# Controller-Board_Rack-PDU_2_0.net
KiCad netlist of a schematic drawn in EAGLE
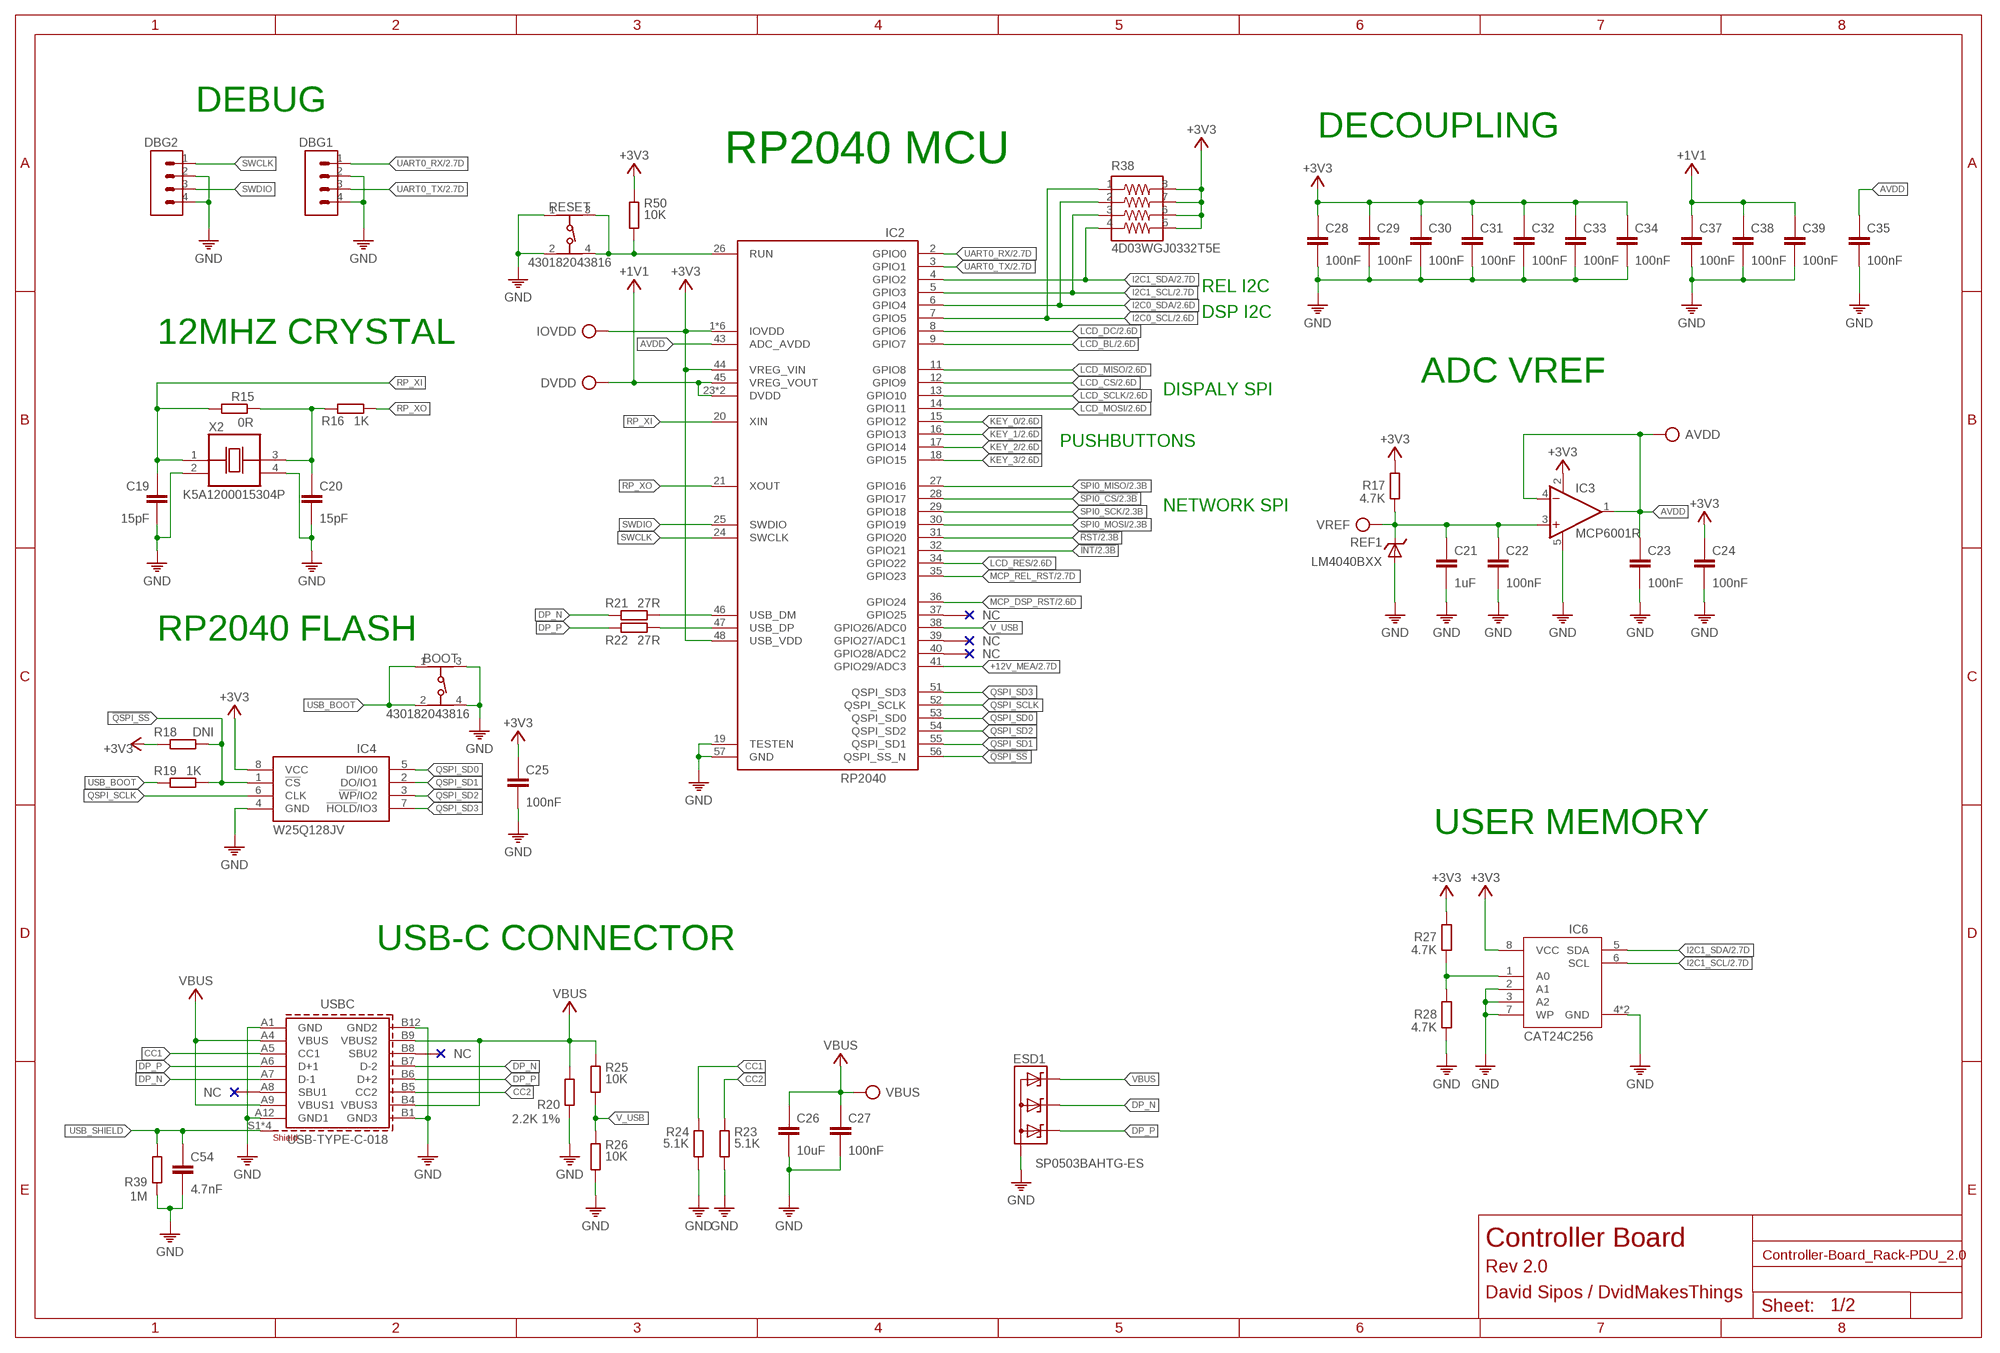
[diagram p0: schematic, sheet 1]
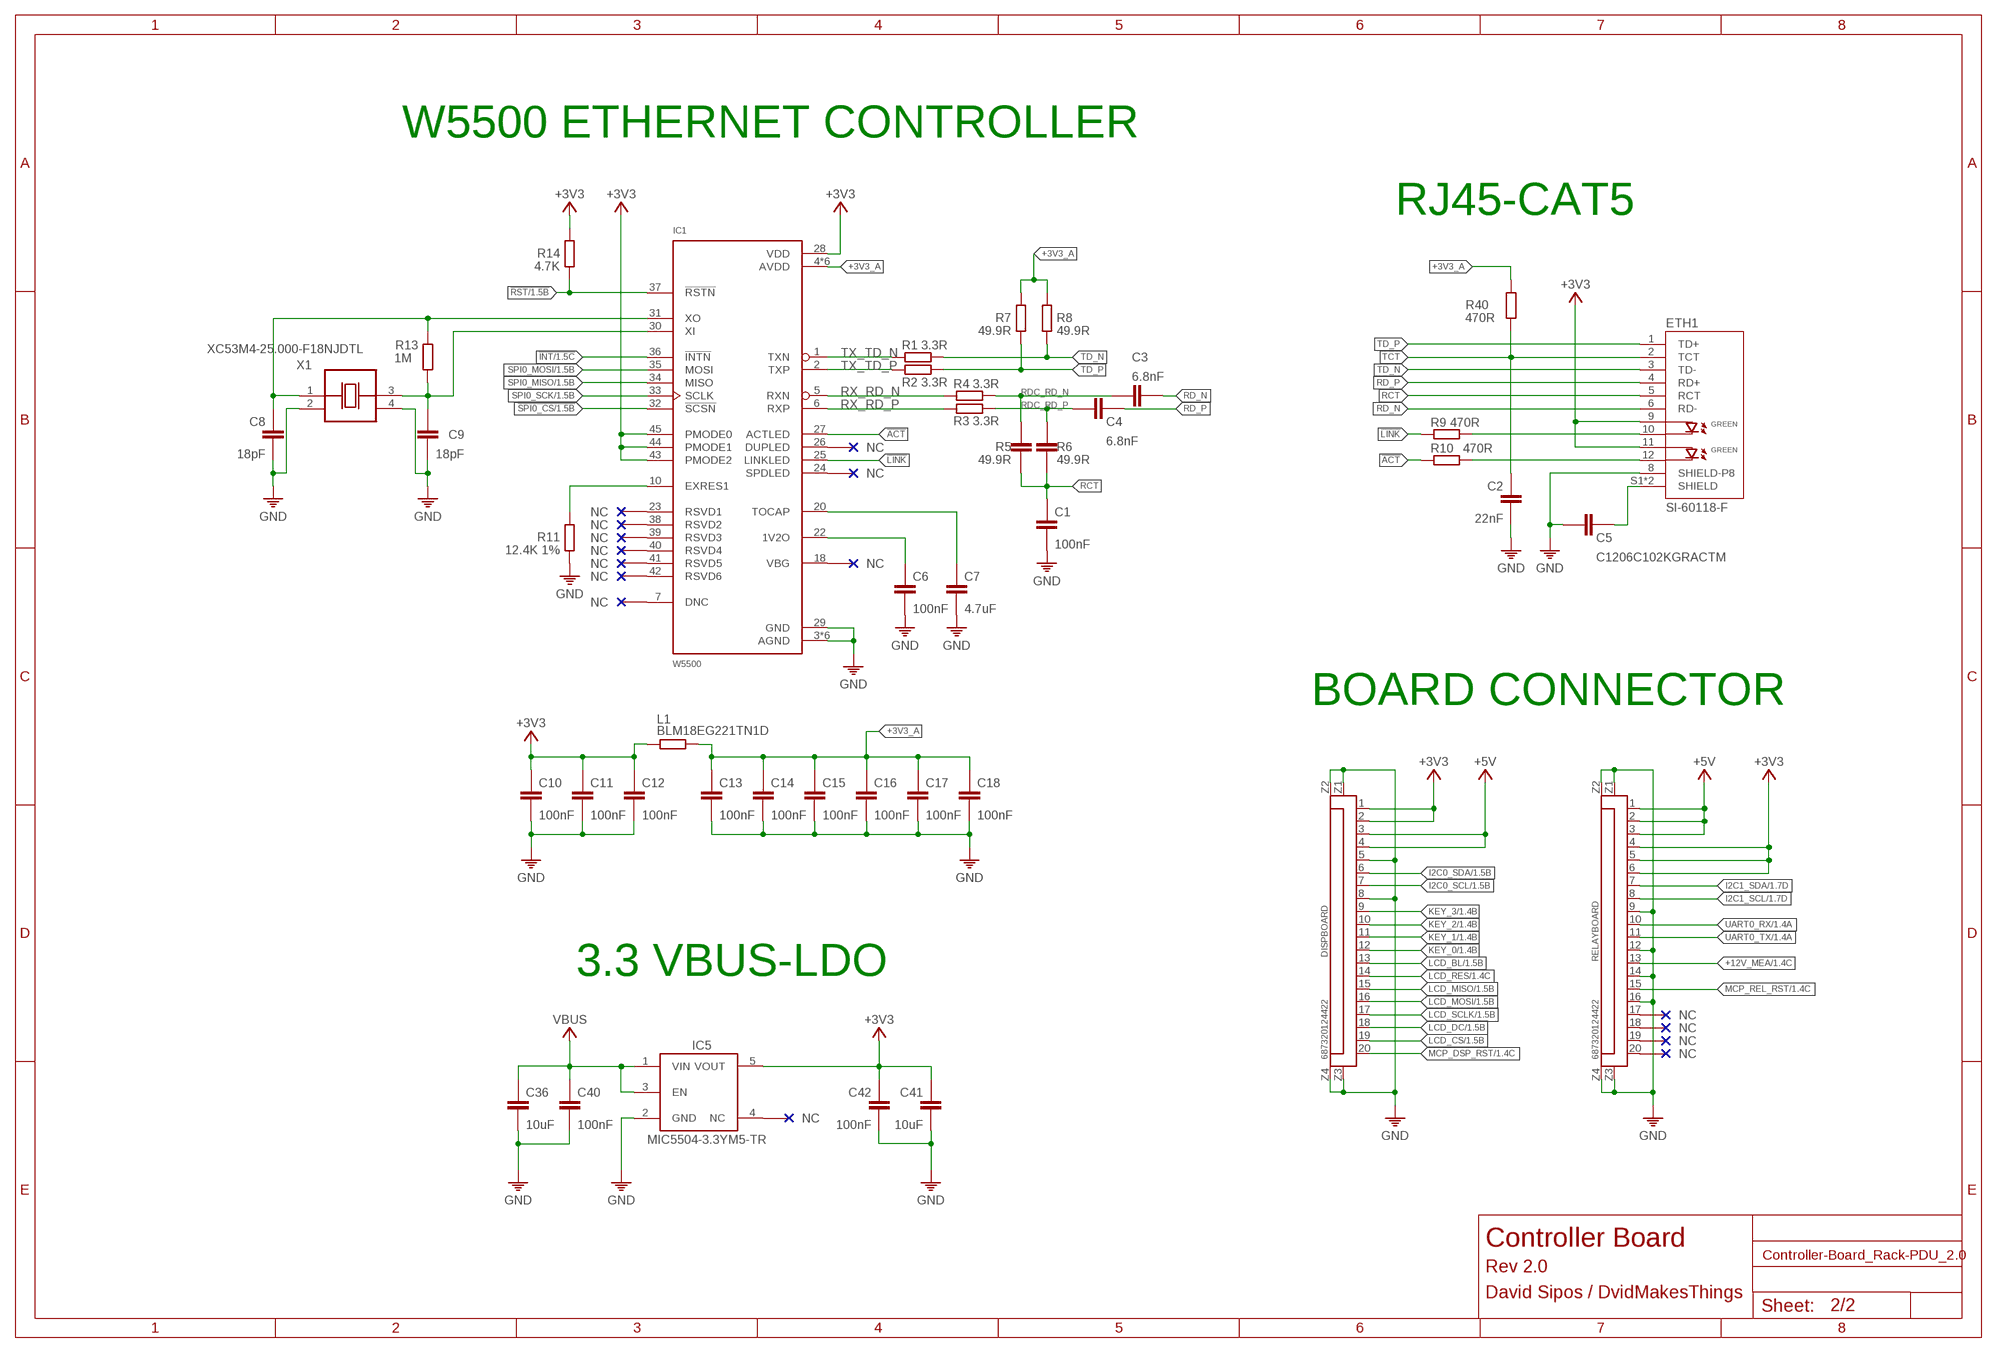
[diagram p1: schematic, sheet 2]

(export (version "E")
  (design (tool "Eeschema 10.0.6"))
  (components
    (comp (ref "AVDD")
      (value "TP")
      (footprint "eagle-import:TP")
      (libsource (lib "eagle-import") (part "TP"))
    )
    (comp (ref "BOOT")
      (value "430182043816")
      (footprint "eagle-import:430182043816")
      (libsource (lib "eagle-import") (part "430182043816"))
    )
    (comp (ref "C19")
      (value "15pF")
      (footprint "eagle-import:C0402")
      (libsource (lib "eagle-import") (part "C-0402"))
    )
    (comp (ref "C20")
      (value "15pF")
      (footprint "eagle-import:C0402")
      (libsource (lib "eagle-import") (part "C-0402"))
    )
    (comp (ref "C21")
      (value "1uF")
      (footprint "eagle-import:C0402")
      (libsource (lib "eagle-import") (part "C-0402"))
    )
    (comp (ref "C22")
      (value "100nF")
      (footprint "eagle-import:C0402")
      (libsource (lib "eagle-import") (part "C-0402"))
    )
    (comp (ref "C23")
      (value "100nF")
      (footprint "eagle-import:C0402")
      (libsource (lib "eagle-import") (part "C-0402"))
    )
    (comp (ref "C24")
      (value "100nF")
      (footprint "eagle-import:C0402")
      (libsource (lib "eagle-import") (part "C-0402"))
    )
    (comp (ref "C25")
      (value "100nF")
      (footprint "eagle-import:C0402")
      (libsource (lib "eagle-import") (part "C-0402"))
    )
    (comp (ref "C26")
      (value "10uF")
      (footprint "eagle-import:0805")
      (libsource (lib "eagle-import") (part "C0805"))
    )
    (comp (ref "C27")
      (value "100nF")
      (footprint "eagle-import:0402")
      (libsource (lib "eagle-import") (part "C0402"))
    )
    (comp (ref "C28")
      (value "100nF")
      (footprint "eagle-import:C0402")
      (libsource (lib "eagle-import") (part "C-0402"))
    )
    (comp (ref "C29")
      (value "100nF")
      (footprint "eagle-import:C0402")
      (libsource (lib "eagle-import") (part "C-0402"))
    )
    (comp (ref "C30")
      (value "100nF")
      (footprint "eagle-import:C0402")
      (libsource (lib "eagle-import") (part "C-0402"))
    )
    (comp (ref "C31")
      (value "100nF")
      (footprint "eagle-import:C0402")
      (libsource (lib "eagle-import") (part "C-0402"))
    )
    (comp (ref "C32")
      (value "100nF")
      (footprint "eagle-import:C0402")
      (libsource (lib "eagle-import") (part "C-0402"))
    )
    (comp (ref "C33")
      (value "100nF")
      (footprint "eagle-import:C0402")
      (libsource (lib "eagle-import") (part "C-0402"))
    )
    (comp (ref "C34")
      (value "100nF")
      (footprint "eagle-import:C0402")
      (libsource (lib "eagle-import") (part "C-0402"))
    )
    (comp (ref "C35")
      (value "100nF")
      (footprint "eagle-import:C0402")
      (libsource (lib "eagle-import") (part "C-0402"))
    )
    (comp (ref "C37")
      (value "100nF")
      (footprint "eagle-import:C0402")
      (libsource (lib "eagle-import") (part "C-0402"))
    )
    (comp (ref "C38")
      (value "100nF")
      (footprint "eagle-import:C0402")
      (libsource (lib "eagle-import") (part "C-0402"))
    )
    (comp (ref "C39")
      (value "100nF")
      (footprint "eagle-import:C0402")
      (libsource (lib "eagle-import") (part "C-0402"))
    )
    (comp (ref "C54")
      (value "4.7nF")
      (footprint "eagle-import:0402")
      (libsource (lib "eagle-import") (part "C0402"))
    )
    (comp (ref "DBG1")
      (value "CON-1X4")
      (footprint "eagle-import:1X4")
      (libsource (lib "eagle-import") (part "CON-1X4"))
    )
    (comp (ref "DBG2")
      (value "CON-1X4")
      (footprint "eagle-import:1X4")
      (libsource (lib "eagle-import") (part "CON-1X4"))
    )
    (comp (ref "DVDD")
      (value "TP")
      (footprint "eagle-import:TP")
      (libsource (lib "eagle-import") (part "TP"))
    )
    (comp (ref "ESD1")
      (value "SP0503BAHTG-ES")
      (footprint "eagle-import:SOT143")
      (libsource (lib "eagle-import") (part "SP0503BAHT"))
    )
    (comp (ref "IC2")
      (value "RP2040")
      (footprint "eagle-import:QFN40P700X700X100-57T510")
      (libsource (lib "eagle-import") (part "RP2040"))
    )
    (comp (ref "IC3")
      (value "MCP6001R")
      (footprint "eagle-import:SOT23-5")
      (libsource (lib "eagle-import") (part "MCP6001RT"))
    )
    (comp (ref "IC4")
      (value "W25Q128JVPIQ")
      (footprint "eagle-import:SON127P600X500X75-8N")
      (libsource (lib "eagle-import") (part "W25Q128JVP"))
    )
    (comp (ref "IC6")
      (value "CAT24C256HU4IGT3")
      (footprint "eagle-import:SON50P300X200X50-9T130X140N")
      (libsource (lib "eagle-import") (part "CAT24C256-HU4"))
    )
    (comp (ref "IOVDD")
      (value "TP")
      (footprint "eagle-import:TP")
      (libsource (lib "eagle-import") (part "TP"))
    )
    (comp (ref "R15")
      (value "0R")
      (footprint "eagle-import:0402")
      (libsource (lib "eagle-import") (part "R0402"))
    )
    (comp (ref "R16")
      (value "1K")
      (footprint "eagle-import:0402")
      (libsource (lib "eagle-import") (part "R0402"))
    )
    (comp (ref "R17")
      (value "4.7K")
      (footprint "eagle-import:0402")
      (libsource (lib "eagle-import") (part "R0402"))
    )
    (comp (ref "R18")
      (value "DNI")
      (footprint "eagle-import:0402")
      (libsource (lib "eagle-import") (part "R0402"))
    )
    (comp (ref "R19")
      (value "1K")
      (footprint "eagle-import:0402")
      (libsource (lib "eagle-import") (part "R0402"))
    )
    (comp (ref "R20")
      (value "2.2K 1%")
      (footprint "eagle-import:0402")
      (libsource (lib "eagle-import") (part "ds_passive_46685041_R0402"))
    )
    (comp (ref "R21")
      (value "27R")
      (footprint "eagle-import:0402")
      (libsource (lib "eagle-import") (part "R0402"))
    )
    (comp (ref "R22")
      (value "27R")
      (footprint "eagle-import:0402")
      (libsource (lib "eagle-import") (part "R0402"))
    )
    (comp (ref "R23")
      (value "5.1K")
      (footprint "eagle-import:0402")
      (libsource (lib "eagle-import") (part "ds_passive_46685041_R0402"))
    )
    (comp (ref "R24")
      (value "5.1K")
      (footprint "eagle-import:0402")
      (libsource (lib "eagle-import") (part "ds_passive_46685041_R0402"))
    )
    (comp (ref "R25")
      (value "10K")
      (footprint "eagle-import:0402")
      (libsource (lib "eagle-import") (part "ds_passive_46685041_R0402"))
    )
    (comp (ref "R26")
      (value "10K")
      (footprint "eagle-import:0402")
      (libsource (lib "eagle-import") (part "ds_passive_46685041_R0402"))
    )
    (comp (ref "R27")
      (value "4.7K")
      (footprint "eagle-import:0402")
      (libsource (lib "eagle-import") (part "R0402"))
    )
    (comp (ref "R28")
      (value "4.7K")
      (footprint "eagle-import:0402")
      (libsource (lib "eagle-import") (part "R0402"))
    )
    (comp (ref "R38")
      (value "4D03WGJ0332T5E")
      (footprint "eagle-import:742C083103JP")
      (fields
        (field (name "MANUFACTURER") "CTS Resistor Products")
        (field (name "MPN") "742C083103JP")
        (field (name "CREATED_BY") "PCBLayout.com")
      )
      (libsource (lib "eagle-import") (part "742C083103JP"))
    )
    (comp (ref "R39")
      (value "1M")
      (footprint "eagle-import:0402")
      (libsource (lib "eagle-import") (part "ds_passive_46685041_R0402"))
    )
    (comp (ref "R50")
      (value "10K")
      (footprint "eagle-import:0402")
      (libsource (lib "eagle-import") (part "ds_passive_46685041_R0402"))
    )
    (comp (ref "REF1")
      (value "LM4040BXX")
      (footprint "eagle-import:SOT23")
      (libsource (lib "eagle-import") (part "LM4040BXX"))
    )
    (comp (ref "RESET")
      (value "430182043816")
      (footprint "eagle-import:430182043816")
      (libsource (lib "eagle-import") (part "430182043816"))
    )
    (comp (ref "USBC")
      (value "USB-TYPE-C-018")
      (footprint "eagle-import:629722000214")
      (libsource (lib "eagle-import") (part "629722000214"))
    )
    (comp (ref "VBUS")
      (value "TP")
      (footprint "eagle-import:TP")
      (libsource (lib "eagle-import") (part "TP"))
    )
    (comp (ref "VREF")
      (value "TP")
      (footprint "eagle-import:TP")
      (libsource (lib "eagle-import") (part "TP"))
    )
    (comp (ref "X2")
      (value "K5A1200015304P")
      (footprint "eagle-import:OSCCC500X320X130")
      (libsource (lib "eagle-import") (part "CRYSTAL"))
    )
    (comp (ref "C1")
      (value "100nF")
      (footprint "eagle-import:C0402")
      (libsource (lib "eagle-import") (part "C-0402"))
    )
    (comp (ref "C2")
      (value "22nF")
      (footprint "eagle-import:C0402")
      (libsource (lib "eagle-import") (part "C-0402"))
    )
    (comp (ref "C3")
      (value "6.8nF")
      (footprint "eagle-import:C0402")
      (libsource (lib "eagle-import") (part "C-0402"))
    )
    (comp (ref "C4")
      (value "6.8nF")
      (footprint "eagle-import:C0402")
      (libsource (lib "eagle-import") (part "C-0402"))
    )
    (comp (ref "C5")
      (value "C1206C102KGRACTM")
      (footprint "eagle-import:C1206")
      (libsource (lib "eagle-import") (part "C-1206"))
    )
    (comp (ref "C6")
      (value "100nF")
      (footprint "eagle-import:C0402")
      (libsource (lib "eagle-import") (part "C-0402"))
    )
    (comp (ref "C7")
      (value "4.7uF")
      (footprint "eagle-import:C0402")
      (libsource (lib "eagle-import") (part "C-0402"))
    )
    (comp (ref "C8")
      (value "18pF")
      (footprint "eagle-import:C0402")
      (libsource (lib "eagle-import") (part "C-0402"))
    )
    (comp (ref "C9")
      (value "18pF")
      (footprint "eagle-import:C0402")
      (libsource (lib "eagle-import") (part "C-0402"))
    )
    (comp (ref "C10")
      (value "100nF")
      (footprint "eagle-import:C0402")
      (libsource (lib "eagle-import") (part "C-0402"))
    )
    (comp (ref "C11")
      (value "100nF")
      (footprint "eagle-import:C0402")
      (libsource (lib "eagle-import") (part "C-0402"))
    )
    (comp (ref "C12")
      (value "100nF")
      (footprint "eagle-import:C0402")
      (libsource (lib "eagle-import") (part "C-0402"))
    )
    (comp (ref "C13")
      (value "100nF")
      (footprint "eagle-import:C0402")
      (libsource (lib "eagle-import") (part "C-0402"))
    )
    (comp (ref "C14")
      (value "100nF")
      (footprint "eagle-import:C0402")
      (libsource (lib "eagle-import") (part "C-0402"))
    )
    (comp (ref "C15")
      (value "100nF")
      (footprint "eagle-import:C0402")
      (libsource (lib "eagle-import") (part "C-0402"))
    )
    (comp (ref "C16")
      (value "100nF")
      (footprint "eagle-import:C0402")
      (libsource (lib "eagle-import") (part "C-0402"))
    )
    (comp (ref "C17")
      (value "100nF")
      (footprint "eagle-import:C0402")
      (libsource (lib "eagle-import") (part "C-0402"))
    )
    (comp (ref "C18")
      (value "100nF")
      (footprint "eagle-import:C0402")
      (libsource (lib "eagle-import") (part "C-0402"))
    )
    (comp (ref "C36")
      (value "10uF")
      (footprint "eagle-import:0805")
      (libsource (lib "eagle-import") (part "C0805"))
    )
    (comp (ref "C40")
      (value "100nF")
      (footprint "eagle-import:0402")
      (libsource (lib "eagle-import") (part "C0402"))
    )
    (comp (ref "C41")
      (value "10uF")
      (footprint "eagle-import:0805")
      (libsource (lib "eagle-import") (part "C0805"))
    )
    (comp (ref "C42")
      (value "100nF")
      (footprint "eagle-import:0402")
      (libsource (lib "eagle-import") (part "C0402"))
    )
    (comp (ref "DISPBOARD")
      (value "687320124422")
      (footprint "eagle-import:687320124422")
      (libsource (lib "eagle-import") (part "6873XX124422_687320124422"))
    )
    (comp (ref "ETH1")
      (value "SI-60118-F")
      (footprint "eagle-import:RJ45-CAT5")
      (fields (field (name "MANUFACTURER") "Bel Fuse"))
      (libsource (lib "eagle-import") (part "RJ45-CAT5"))
    )
    (comp (ref "IC1")
      (value "W5500")
      (footprint "eagle-import:LQFP48")
      (libsource (lib "eagle-import") (part "W5500"))
    )
    (comp (ref "IC5")
      (value "MIC5504-3.3YM5-TR")
      (footprint "eagle-import:SOT23-5")
      (libsource (lib "eagle-import") (part "MIC5504-3.3YM5-TR"))
    )
    (comp (ref "L1")
      (value "BLM18EG221TN1D")
      (footprint "eagle-import:0603")
      (libsource (lib "eagle-import") (part "R0603"))
    )
    (comp (ref "R1")
      (value "3.3R")
      (footprint "eagle-import:0402")
      (libsource (lib "eagle-import") (part "R0402"))
    )
    (comp (ref "R2")
      (value "3.3R")
      (footprint "eagle-import:0402")
      (libsource (lib "eagle-import") (part "R0402"))
    )
    (comp (ref "R3")
      (value "3.3R")
      (footprint "eagle-import:0402")
      (libsource (lib "eagle-import") (part "R0402"))
    )
    (comp (ref "R4")
      (value "3.3R")
      (footprint "eagle-import:0402")
      (libsource (lib "eagle-import") (part "R0402"))
    )
    (comp (ref "R5")
      (value "49.9R")
      (footprint "eagle-import:C0402")
      (libsource (lib "eagle-import") (part "C-0402"))
    )
    (comp (ref "R6")
      (value "49.9R")
      (footprint "eagle-import:C0402")
      (libsource (lib "eagle-import") (part "C-0402"))
    )
    (comp (ref "R7")
      (value "49.9R")
      (footprint "eagle-import:0402")
      (libsource (lib "eagle-import") (part "R0402"))
    )
    (comp (ref "R8")
      (value "49.9R")
      (footprint "eagle-import:0402")
      (libsource (lib "eagle-import") (part "R0402"))
    )
    (comp (ref "R9")
      (value "470R")
      (footprint "eagle-import:0402")
      (libsource (lib "eagle-import") (part "R0402"))
    )
    (comp (ref "R10")
      (value "470R")
      (footprint "eagle-import:0402")
      (libsource (lib "eagle-import") (part "R0402"))
    )
    (comp (ref "R11")
      (value "12.4K 1%")
      (footprint "eagle-import:0402")
      (libsource (lib "eagle-import") (part "R0402"))
    )
    (comp (ref "R13")
      (value "1M")
      (footprint "eagle-import:0402")
      (libsource (lib "eagle-import") (part "R0402"))
    )
    (comp (ref "R14")
      (value "4.7K")
      (footprint "eagle-import:0402")
      (libsource (lib "eagle-import") (part "R0402"))
    )
    (comp (ref "R40")
      (value "470R")
      (footprint "eagle-import:0402")
      (libsource (lib "eagle-import") (part "R0402"))
    )
    (comp (ref "RELAYBOARD")
      (value "687320124422")
      (footprint "eagle-import:687320124422")
      (libsource (lib "eagle-import") (part "6873XX124422_687320124422"))
    )
    (comp (ref "X1")
      (value "XC53M4-25.000-F18NJDTL")
      (footprint "eagle-import:OSCCC500X320X130")
      (libsource (lib "eagle-import") (part "CRYSTAL"))
    )
  )
  (nets
    (net (code "1") (name "+1V1") (class "Default")
      (node (ref "C37") (pin "1") (pinfunction "1_1") (pintype "passive"))
      (node (ref "C38") (pin "1") (pinfunction "1_1") (pintype "passive"))
      (node (ref "C39") (pin "1") (pinfunction "1_1") (pintype "passive"))
      (node (ref "DVDD") (pin "TP") (pinfunction "P$1_TP") (pintype "bidirectional"))
      (node (ref "IC2") (pin "23") (pinfunction "DVDD_23") (pintype "bidirectional"))
      (node (ref "IC2") (pin "45") (pinfunction "VREG_VOUT_45") (pintype "bidirectional"))
      (node (ref "IC2") (pin "50") (pinfunction "DVDD_50") (pintype "bidirectional"))
    )
    (net (code "2") (name "+3V3") (class "Default")
      (node (ref "C10") (pin "1") (pinfunction "1_1") (pintype "passive"))
      (node (ref "C11") (pin "1") (pinfunction "1_1") (pintype "passive"))
      (node (ref "C12") (pin "1") (pinfunction "1_1") (pintype "passive"))
      (node (ref "C24") (pin "1") (pinfunction "1_1") (pintype "passive"))
      (node (ref "C25") (pin "1") (pinfunction "1_1") (pintype "passive"))
      (node (ref "C28") (pin "1") (pinfunction "1_1") (pintype "passive"))
      (node (ref "C29") (pin "1") (pinfunction "1_1") (pintype "passive"))
      (node (ref "C30") (pin "1") (pinfunction "1_1") (pintype "passive"))
      (node (ref "C31") (pin "1") (pinfunction "1_1") (pintype "passive"))
      (node (ref "C32") (pin "1") (pinfunction "1_1") (pintype "passive"))
      (node (ref "C33") (pin "1") (pinfunction "1_1") (pintype "passive"))
      (node (ref "C34") (pin "1") (pinfunction "1_1") (pintype "passive"))
      (node (ref "C41") (pin "1") (pinfunction "1_1") (pintype "passive"))
      (node (ref "C42") (pin "1") (pinfunction "1_1") (pintype "passive"))
      (node (ref "DISPBOARD") (pin "1") (pinfunction "1_1") (pintype "passive"))
      (node (ref "DISPBOARD") (pin "2") (pinfunction "2_2") (pintype "passive"))
      (node (ref "ETH1") (pin "11") (pinfunction "GA2_11") (pintype "passive"))
      (node (ref "ETH1") (pin "9") (pinfunction "GA1_9") (pintype "passive"))
      (node (ref "IC1") (pin "28") (pinfunction "VDD_28") (pintype "power_in"))
      (node (ref "IC1") (pin "43") (pinfunction "PMODE2_43") (pintype "input"))
      (node (ref "IC1") (pin "44") (pinfunction "PMODE1_44") (pintype "input"))
      (node (ref "IC1") (pin "45") (pinfunction "PMODE0_45") (pintype "input"))
      (node (ref "IC2") (pin "1") (pinfunction "IOVDD_1") (pintype "bidirectional"))
      (node (ref "IC2") (pin "10") (pinfunction "IOVDD_10") (pintype "bidirectional"))
      (node (ref "IC2") (pin "22") (pinfunction "IOVDD_22") (pintype "bidirectional"))
      (node (ref "IC2") (pin "33") (pinfunction "IOVDD_33") (pintype "bidirectional"))
      (node (ref "IC2") (pin "42") (pinfunction "IOVDD_42") (pintype "bidirectional"))
      (node (ref "IC2") (pin "44") (pinfunction "VREG_VIN_44") (pintype "bidirectional"))
      (node (ref "IC2") (pin "48") (pinfunction "USB_VDD_48") (pintype "bidirectional"))
      (node (ref "IC2") (pin "49") (pinfunction "IOVDD_49") (pintype "bidirectional"))
      (node (ref "IC3") (pin "2") (pinfunction "V+_2") (pintype "power_in"))
      (node (ref "IC4") (pin "8") (pinfunction "VCC_8") (pintype "power_in"))
      (node (ref "IC5") (pin "5") (pinfunction "VOUT_5") (pintype "bidirectional"))
      (node (ref "IC6") (pin "8") (pinfunction "VCC_8") (pintype "power_in"))
      (node (ref "IOVDD") (pin "TP") (pinfunction "P$1_TP") (pintype "bidirectional"))
      (node (ref "L1") (pin "1") (pinfunction "1_1") (pintype "passive"))
      (node (ref "R14") (pin "2") (pinfunction "2_2") (pintype "passive"))
      (node (ref "R17") (pin "2") (pinfunction "2_2") (pintype "passive"))
      (node (ref "R18") (pin "2") (pinfunction "2_2") (pintype "passive"))
      (node (ref "R27") (pin "2") (pinfunction "2_2") (pintype "passive"))
      (node (ref "R38") (pin "5") (pinfunction "5_5") (pintype "passive"))
      (node (ref "R38") (pin "6") (pinfunction "6_6") (pintype "passive"))
      (node (ref "R38") (pin "7") (pinfunction "7_7") (pintype "passive"))
      (node (ref "R38") (pin "8") (pinfunction "8_8") (pintype "passive"))
      (node (ref "R50") (pin "1") (pinfunction "1_1") (pintype "passive"))
      (node (ref "RELAYBOARD") (pin "4") (pinfunction "4_4") (pintype "passive"))
      (node (ref "RELAYBOARD") (pin "5") (pinfunction "5_5") (pintype "passive"))
      (node (ref "RELAYBOARD") (pin "6") (pinfunction "6_6") (pintype "passive"))
    )
    (net (code "3") (name "+3V3_A") (class "Default")
      (node (ref "C13") (pin "1") (pinfunction "1_1") (pintype "passive"))
      (node (ref "C14") (pin "1") (pinfunction "1_1") (pintype "passive"))
      (node (ref "C15") (pin "1") (pinfunction "1_1") (pintype "passive"))
      (node (ref "C16") (pin "1") (pinfunction "1_1") (pintype "passive"))
      (node (ref "C17") (pin "1") (pinfunction "1_1") (pintype "passive"))
      (node (ref "C18") (pin "1") (pinfunction "1_1") (pintype "passive"))
      (node (ref "IC1") (pin "11") (pinfunction "AVDD_11") (pintype "power_in"))
      (node (ref "IC1") (pin "15") (pinfunction "AVDD_15") (pintype "power_in"))
      (node (ref "IC1") (pin "17") (pinfunction "AVDD_17") (pintype "power_in"))
      (node (ref "IC1") (pin "21") (pinfunction "AVDD_21") (pintype "power_in"))
      (node (ref "IC1") (pin "4") (pinfunction "AVDD_4") (pintype "power_in"))
      (node (ref "IC1") (pin "8") (pinfunction "AVDD_8") (pintype "power_in"))
      (node (ref "L1") (pin "2") (pinfunction "2_2") (pintype "passive"))
      (node (ref "R40") (pin "2") (pinfunction "2_2") (pintype "passive"))
      (node (ref "R7") (pin "2") (pinfunction "2_2") (pintype "passive"))
      (node (ref "R8") (pin "2") (pinfunction "2_2") (pintype "passive"))
    )
    (net (code "4") (name "+5V") (class "Default")
      (node (ref "DISPBOARD") (pin "3") (pinfunction "3_3") (pintype "passive"))
      (node (ref "DISPBOARD") (pin "4") (pinfunction "4_4") (pintype "passive"))
      (node (ref "RELAYBOARD") (pin "1") (pinfunction "1_1") (pintype "passive"))
      (node (ref "RELAYBOARD") (pin "2") (pinfunction "2_2") (pintype "passive"))
      (node (ref "RELAYBOARD") (pin "3") (pinfunction "3_3") (pintype "passive"))
    )
    (net (code "5") (name "+12V_MEA") (class "Default")
      (node (ref "IC2") (pin "41") (pinfunction "GPIO29/ADC3_41") (pintype "bidirectional"))
      (node (ref "RELAYBOARD") (pin "13") (pinfunction "13_13") (pintype "passive"))
    )
    (net (code "6") (name "AVDD") (class "Default")
      (node (ref "AVDD") (pin "TP") (pinfunction "P$1_TP") (pintype "bidirectional"))
      (node (ref "C23") (pin "1") (pinfunction "1_1") (pintype "passive"))
      (node (ref "C35") (pin "1") (pinfunction "1_1") (pintype "passive"))
      (node (ref "IC2") (pin "43") (pinfunction "ADC_AVDD_43") (pintype "bidirectional"))
      (node (ref "IC3") (pin "1") (pinfunction "OUT_1") (pintype "output"))
      (node (ref "IC3") (pin "4") (pinfunction "-IN_4") (pintype "input"))
    )
    (net (code "7") (name "CC1") (class "Default")
      (node (ref "R24") (pin "1") (pinfunction "1_1") (pintype "passive"))
      (node (ref "USBC") (pin "A5") (pinfunction "CC1_A5") (pintype "passive"))
    )
    (net (code "8") (name "CC2") (class "Default")
      (node (ref "R23") (pin "1") (pinfunction "1_1") (pintype "passive"))
      (node (ref "USBC") (pin "B5") (pinfunction "CC2_B5") (pintype "passive"))
    )
    (net (code "9") (name "DP_N") (class "Default")
      (node (ref "ESD1") (pin "3") (pinfunction "C2_3") (pintype "bidirectional"))
      (node (ref "R21") (pin "1") (pinfunction "1_1") (pintype "passive"))
      (node (ref "USBC") (pin "A7") (pinfunction "D-1_A7") (pintype "passive"))
      (node (ref "USBC") (pin "B7") (pinfunction "D-2_B7") (pintype "passive"))
    )
    (net (code "10") (name "DP_P") (class "Default")
      (node (ref "ESD1") (pin "2") (pinfunction "C1_2") (pintype "bidirectional"))
      (node (ref "R22") (pin "1") (pinfunction "1_1") (pintype "passive"))
      (node (ref "USBC") (pin "A6") (pinfunction "D+1_A6") (pintype "passive"))
      (node (ref "USBC") (pin "B6") (pinfunction "D+2_B6") (pintype "passive"))
    )
    (net (code "11") (name "GND") (class "Default")
      (node (ref "BOOT") (pin "3") (pinfunction "3_3") (pintype "passive"))
      (node (ref "BOOT") (pin "4") (pinfunction "4_4") (pintype "passive"))
      (node (ref "C1") (pin "2") (pinfunction "2_2") (pintype "passive"))
      (node (ref "C10") (pin "2") (pinfunction "2_2") (pintype "passive"))
      (node (ref "C11") (pin "2") (pinfunction "2_2") (pintype "passive"))
      (node (ref "C12") (pin "2") (pinfunction "2_2") (pintype "passive"))
      (node (ref "C13") (pin "2") (pinfunction "2_2") (pintype "passive"))
      (node (ref "C14") (pin "2") (pinfunction "2_2") (pintype "passive"))
      (node (ref "C15") (pin "2") (pinfunction "2_2") (pintype "passive"))
      (node (ref "C16") (pin "2") (pinfunction "2_2") (pintype "passive"))
      (node (ref "C17") (pin "2") (pinfunction "2_2") (pintype "passive"))
      (node (ref "C18") (pin "2") (pinfunction "2_2") (pintype "passive"))
      (node (ref "C19") (pin "2") (pinfunction "2_2") (pintype "passive"))
      (node (ref "C2") (pin "2") (pinfunction "2_2") (pintype "passive"))
      (node (ref "C20") (pin "2") (pinfunction "2_2") (pintype "passive"))
      (node (ref "C21") (pin "2") (pinfunction "2_2") (pintype "passive"))
      (node (ref "C22") (pin "2") (pinfunction "2_2") (pintype "passive"))
      (node (ref "C23") (pin "2") (pinfunction "2_2") (pintype "passive"))
      (node (ref "C24") (pin "2") (pinfunction "2_2") (pintype "passive"))
      (node (ref "C25") (pin "2") (pinfunction "2_2") (pintype "passive"))
      (node (ref "C26") (pin "2") (pinfunction "2_2") (pintype "passive"))
      (node (ref "C27") (pin "2") (pinfunction "2_2") (pintype "passive"))
      (node (ref "C28") (pin "2") (pinfunction "2_2") (pintype "passive"))
      (node (ref "C29") (pin "2") (pinfunction "2_2") (pintype "passive"))
      (node (ref "C30") (pin "2") (pinfunction "2_2") (pintype "passive"))
      (node (ref "C31") (pin "2") (pinfunction "2_2") (pintype "passive"))
      (node (ref "C32") (pin "2") (pinfunction "2_2") (pintype "passive"))
      (node (ref "C33") (pin "2") (pinfunction "2_2") (pintype "passive"))
      (node (ref "C34") (pin "2") (pinfunction "2_2") (pintype "passive"))
      (node (ref "C35") (pin "2") (pinfunction "2_2") (pintype "passive"))
      (node (ref "C36") (pin "2") (pinfunction "2_2") (pintype "passive"))
      (node (ref "C37") (pin "2") (pinfunction "2_2") (pintype "passive"))
      (node (ref "C38") (pin "2") (pinfunction "2_2") (pintype "passive"))
      (node (ref "C39") (pin "2") (pinfunction "2_2") (pintype "passive"))
      (node (ref "C40") (pin "2") (pinfunction "2_2") (pintype "passive"))
      (node (ref "C41") (pin "2") (pinfunction "2_2") (pintype "passive"))
      (node (ref "C42") (pin "2") (pinfunction "2_2") (pintype "passive"))
      (node (ref "C5") (pin "1") (pinfunction "1_1") (pintype "passive"))
      (node (ref "C54") (pin "2") (pinfunction "2_2") (pintype "passive"))
      (node (ref "C6") (pin "2") (pinfunction "2_2") (pintype "passive"))
      (node (ref "C7") (pin "2") (pinfunction "2_2") (pintype "passive"))
      (node (ref "C8") (pin "2") (pinfunction "2_2") (pintype "passive"))
      (node (ref "C9") (pin "2") (pinfunction "2_2") (pintype "passive"))
      (node (ref "DBG1") (pin "2") (pinfunction "P$2_2") (pintype "bidirectional"))
      (node (ref "DBG1") (pin "4") (pinfunction "P$4_4") (pintype "bidirectional"))
      (node (ref "DBG2") (pin "2") (pinfunction "P$2_2") (pintype "bidirectional"))
      (node (ref "DBG2") (pin "4") (pinfunction "P$4_4") (pintype "bidirectional"))
      (node (ref "DISPBOARD") (pin "5") (pinfunction "5_5") (pintype "passive"))
      (node (ref "DISPBOARD") (pin "8") (pinfunction "8_8") (pintype "passive"))
      (node (ref "DISPBOARD") (pin "Z1") (pinfunction "Z1_Z1") (pintype "passive"))
      (node (ref "DISPBOARD") (pin "Z2") (pinfunction "Z2_Z2") (pintype "passive"))
      (node (ref "DISPBOARD") (pin "Z3") (pinfunction "Z3_Z3") (pintype "passive"))
      (node (ref "DISPBOARD") (pin "Z4") (pinfunction "Z4_Z4") (pintype "passive"))
      (node (ref "ESD1") (pin "1") (pinfunction "A_1") (pintype "bidirectional"))
      (node (ref "ETH1") (pin "8") (pinfunction "SHIELD-P8_8") (pintype "passive"))
      (node (ref "IC1") (pin "14") (pinfunction "AGND_14") (pintype "power_in"))
      (node (ref "IC1") (pin "16") (pinfunction "AGND_16") (pintype "power_in"))
      (node (ref "IC1") (pin "19") (pinfunction "AGND_19") (pintype "power_in"))
      (node (ref "IC1") (pin "29") (pinfunction "GND_29") (pintype "passive"))
      (node (ref "IC1") (pin "3") (pinfunction "AGND_3") (pintype "power_in"))
      (node (ref "IC1") (pin "48") (pinfunction "AGND_48") (pintype "power_in"))
      (node (ref "IC1") (pin "9") (pinfunction "AGND_9") (pintype "power_in"))
      (node (ref "IC2") (pin "19") (pinfunction "TESTEN_19") (pintype "bidirectional"))
      (node (ref "IC2") (pin "57") (pinfunction "GND_57") (pintype "bidirectional"))
      (node (ref "IC3") (pin "5") (pinfunction "V-_5") (pintype "power_in"))
      (node (ref "IC4") (pin "4") (pinfunction "GND_4") (pintype "power_in"))
      (node (ref "IC5") (pin "2") (pinfunction "GND_2") (pintype "bidirectional"))
      (node (ref "IC6") (pin "2") (pinfunction "A1_2") (pintype "bidirectional"))
      (node (ref "IC6") (pin "3") (pinfunction "A2_3") (pintype "bidirectional"))
      (node (ref "IC6") (pin "4") (pinfunction "GND_4") (pintype "power_in"))
      (node (ref "IC6") (pin "7") (pinfunction "WP_7") (pintype "bidirectional"))
      (node (ref "IC6") (pin "9") (pinfunction "GND_9") (pintype "power_in"))
      (node (ref "R11") (pin "1") (pinfunction "1_1") (pintype "passive"))
      (node (ref "R20") (pin "2") (pinfunction "2_2") (pintype "passive"))
      (node (ref "R23") (pin "2") (pinfunction "2_2") (pintype "passive"))
      (node (ref "R24") (pin "2") (pinfunction "2_2") (pintype "passive"))
      (node (ref "R26") (pin "2") (pinfunction "2_2") (pintype "passive"))
      (node (ref "R28") (pin "1") (pinfunction "1_1") (pintype "passive"))
      (node (ref "R39") (pin "2") (pinfunction "2_2") (pintype "passive"))
      (node (ref "REF1") (pin "2") (pinfunction "A_2") (pintype "passive"))
      (node (ref "REF1") (pin "3") (pinfunction "A_3") (pintype "passive"))
      (node (ref "RELAYBOARD") (pin "12") (pinfunction "12_12") (pintype "passive"))
      (node (ref "RELAYBOARD") (pin "14") (pinfunction "14_14") (pintype "passive"))
      (node (ref "RELAYBOARD") (pin "16") (pinfunction "16_16") (pintype "passive"))
      (node (ref "RELAYBOARD") (pin "9") (pinfunction "9_9") (pintype "passive"))
      (node (ref "RELAYBOARD") (pin "Z1") (pinfunction "Z1_Z1") (pintype "passive"))
      (node (ref "RELAYBOARD") (pin "Z2") (pinfunction "Z2_Z2") (pintype "passive"))
      (node (ref "RELAYBOARD") (pin "Z3") (pinfunction "Z3_Z3") (pintype "passive"))
      (node (ref "RELAYBOARD") (pin "Z4") (pinfunction "Z4_Z4") (pintype "passive"))
      (node (ref "RESET") (pin "1") (pinfunction "1_1") (pintype "passive"))
      (node (ref "RESET") (pin "2") (pinfunction "2_2") (pintype "passive"))
      (node (ref "USBC") (pin "A1") (pinfunction "GND_A1") (pintype "passive"))
      (node (ref "USBC") (pin "A12") (pinfunction "GND1_A12") (pintype "passive"))
      (node (ref "USBC") (pin "B1") (pinfunction "GND3_B1") (pintype "passive"))
      (node (ref "USBC") (pin "B12") (pinfunction "GND2_B12") (pintype "passive"))
      (node (ref "X1") (pin "2") (pinfunction "VSS_2") (pintype "power_in"))
      (node (ref "X1") (pin "4") (pinfunction "VDD_4") (pintype "power_in"))
      (node (ref "X2") (pin "2") (pinfunction "VSS_2") (pintype "power_in"))
      (node (ref "X2") (pin "4") (pinfunction "VDD_4") (pintype "power_in"))
    )
    (net (code "12") (name "I2C0_SCL") (class "Default")
      (node (ref "DISPBOARD") (pin "7") (pinfunction "7_7") (pintype "passive"))
      (node (ref "IC2") (pin "7") (pinfunction "GPIO5_7") (pintype "bidirectional"))
      (node (ref "R38") (pin "1") (pinfunction "1_1") (pintype "passive"))
    )
    (net (code "13") (name "I2C0_SDA") (class "Default")
      (node (ref "DISPBOARD") (pin "6") (pinfunction "6_6") (pintype "passive"))
      (node (ref "IC2") (pin "6") (pinfunction "GPIO4_6") (pintype "bidirectional"))
      (node (ref "R38") (pin "2") (pinfunction "2_2") (pintype "passive"))
    )
    (net (code "14") (name "I2C1_SCL") (class "Default")
      (node (ref "IC2") (pin "5") (pinfunction "GPIO3_5") (pintype "bidirectional"))
      (node (ref "IC6") (pin "6") (pinfunction "SCL_6") (pintype "bidirectional"))
      (node (ref "R38") (pin "3") (pinfunction "3_3") (pintype "passive"))
      (node (ref "RELAYBOARD") (pin "8") (pinfunction "8_8") (pintype "passive"))
    )
    (net (code "15") (name "I2C1_SDA") (class "Default")
      (node (ref "IC2") (pin "4") (pinfunction "GPIO2_4") (pintype "bidirectional"))
      (node (ref "IC6") (pin "5") (pinfunction "SDA_5") (pintype "bidirectional"))
      (node (ref "R38") (pin "4") (pinfunction "4_4") (pintype "passive"))
      (node (ref "RELAYBOARD") (pin "7") (pinfunction "7_7") (pintype "passive"))
    )
    (net (code "16") (name "KEY_0") (class "Default")
      (node (ref "DISPBOARD") (pin "12") (pinfunction "12_12") (pintype "passive"))
      (node (ref "IC2") (pin "15") (pinfunction "GPIO12_15") (pintype "bidirectional"))
    )
    (net (code "17") (name "KEY_1") (class "Default")
      (node (ref "DISPBOARD") (pin "11") (pinfunction "11_11") (pintype "passive"))
      (node (ref "IC2") (pin "16") (pinfunction "GPIO13_16") (pintype "bidirectional"))
    )
    (net (code "18") (name "KEY_2") (class "Default")
      (node (ref "DISPBOARD") (pin "10") (pinfunction "10_10") (pintype "passive"))
      (node (ref "IC2") (pin "17") (pinfunction "GPIO14_17") (pintype "bidirectional"))
    )
    (net (code "19") (name "KEY_3") (class "Default")
      (node (ref "DISPBOARD") (pin "9") (pinfunction "9_9") (pintype "passive"))
      (node (ref "IC2") (pin "18") (pinfunction "GPIO15_18") (pintype "bidirectional"))
    )
    (net (code "20") (name "LCD_BL") (class "Default")
      (node (ref "DISPBOARD") (pin "13") (pinfunction "13_13") (pintype "passive"))
      (node (ref "IC2") (pin "9") (pinfunction "GPIO7_9") (pintype "bidirectional"))
    )
    (net (code "21") (name "LCD_CS") (class "Default")
      (node (ref "DISPBOARD") (pin "19") (pinfunction "19_19") (pintype "passive"))
      (node (ref "IC2") (pin "12") (pinfunction "GPIO9_12") (pintype "bidirectional"))
    )
    (net (code "22") (name "LCD_DC") (class "Default")
      (node (ref "DISPBOARD") (pin "18") (pinfunction "18_18") (pintype "passive"))
      (node (ref "IC2") (pin "8") (pinfunction "GPIO6_8") (pintype "bidirectional"))
    )
    (net (code "23") (name "LCD_MISO") (class "Default")
      (node (ref "DISPBOARD") (pin "15") (pinfunction "15_15") (pintype "passive"))
      (node (ref "IC2") (pin "11") (pinfunction "GPIO8_11") (pintype "bidirectional"))
    )
    (net (code "24") (name "LCD_MOSI") (class "Default")
      (node (ref "DISPBOARD") (pin "16") (pinfunction "16_16") (pintype "passive"))
      (node (ref "IC2") (pin "14") (pinfunction "GPIO11_14") (pintype "bidirectional"))
    )
    (net (code "25") (name "LCD_RES") (class "Default")
      (node (ref "DISPBOARD") (pin "14") (pinfunction "14_14") (pintype "passive"))
      (node (ref "IC2") (pin "34") (pinfunction "GPIO22_34") (pintype "bidirectional"))
    )
    (net (code "26") (name "LCD_SCLK") (class "Default")
      (node (ref "DISPBOARD") (pin "17") (pinfunction "17_17") (pintype "passive"))
      (node (ref "IC2") (pin "13") (pinfunction "GPIO10_13") (pintype "bidirectional"))
    )
    (net (code "27") (name "MCP_DSP_RST") (class "Default")
      (node (ref "DISPBOARD") (pin "20") (pinfunction "20_20") (pintype "passive"))
      (node (ref "IC2") (pin "36") (pinfunction "GPIO24_36") (pintype "bidirectional"))
    )
    (net (code "28") (name "MCP_REL_RST") (class "Default")
      (node (ref "IC2") (pin "35") (pinfunction "GPIO23_35") (pintype "bidirectional"))
      (node (ref "RELAYBOARD") (pin "15") (pinfunction "15_15") (pintype "passive"))
    )
    (net (code "29") (name "Net-(C5-Pad2)") (class "Default")
      (node (ref "C5") (pin "2") (pinfunction "2_2") (pintype "passive"))
      (node (ref "ETH1") (pin "S1") (pinfunction "SHIELD_S1") (pintype "passive"))
      (node (ref "ETH1") (pin "S2") (pinfunction "SHIELD_S2") (pintype "passive"))
    )
    (net (code "30") (name "Net-(ETH1-GK1)") (class "Default")
      (node (ref "ETH1") (pin "10") (pinfunction "GK1_10") (pintype "passive"))
      (node (ref "R9") (pin "2") (pinfunction "2_2") (pintype "passive"))
    )
    (net (code "31") (name "Net-(ETH1-GK2)") (class "Default")
      (node (ref "ETH1") (pin "12") (pinfunction "GK2_12") (pintype "passive"))
      (node (ref "R10") (pin "2") (pinfunction "2_2") (pintype "passive"))
    )
    (net (code "32") (name "Net-(IC1-1V2O)") (class "Default")
      (node (ref "C6") (pin "1") (pinfunction "1_1") (pintype "passive"))
      (node (ref "IC1") (pin "22") (pinfunction "1V2O_22") (pintype "output"))
    )
    (net (code "33") (name "Net-(IC1-EXRES1)") (class "Default")
      (node (ref "IC1") (pin "10") (pinfunction "EXRES1_10") (pintype "bidirectional"))
      (node (ref "R11") (pin "2") (pinfunction "2_2") (pintype "passive"))
    )
    (net (code "34") (name "Net-(IC1-TOCAP)") (class "Default")
      (node (ref "C7") (pin "1") (pinfunction "1_1") (pintype "passive"))
      (node (ref "IC1") (pin "20") (pinfunction "TOCAP_20") (pintype "output"))
    )
    (net (code "35") (name "Net-(IC1-XI)") (class "Default")
      (node (ref "C9") (pin "1") (pinfunction "1_1") (pintype "passive"))
      (node (ref "IC1") (pin "30") (pinfunction "XI_30") (pintype "input"))
      (node (ref "R13") (pin "1") (pinfunction "1_1") (pintype "passive"))
      (node (ref "X1") (pin "3") (pinfunction "OUT_3") (pintype "output"))
    )
    (net (code "36") (name "Net-(IC1-XO)") (class "Default")
      (node (ref "C8") (pin "1") (pinfunction "1_1") (pintype "passive"))
      (node (ref "IC1") (pin "31") (pinfunction "XO_31") (pintype "output"))
      (node (ref "R13") (pin "2") (pinfunction "2_2") (pintype "passive"))
      (node (ref "X1") (pin "1") (pinfunction "CON_1") (pintype "input"))
    )
    (net (code "37") (name "Net-(IC2-RUN)") (class "Default")
      (node (ref "IC2") (pin "26") (pinfunction "RUN_26") (pintype "bidirectional"))
      (node (ref "R50") (pin "2") (pinfunction "2_2") (pintype "passive"))
      (node (ref "RESET") (pin "3") (pinfunction "3_3") (pintype "passive"))
      (node (ref "RESET") (pin "4") (pinfunction "4_4") (pintype "passive"))
    )
    (net (code "38") (name "Net-(IC2-USB_DM)") (class "Default")
      (node (ref "IC2") (pin "46") (pinfunction "USB_DM_46") (pintype "bidirectional"))
      (node (ref "R21") (pin "2") (pinfunction "2_2") (pintype "passive"))
    )
    (net (code "39") (name "Net-(IC2-USB_DP)") (class "Default")
      (node (ref "IC2") (pin "47") (pinfunction "USB_DP_47") (pintype "bidirectional"))
      (node (ref "R22") (pin "2") (pinfunction "2_2") (pintype "passive"))
    )
    (net (code "40") (name "Net-(IC3-+IN)") (class "Default")
      (node (ref "C21") (pin "1") (pinfunction "1_1") (pintype "passive"))
      (node (ref "C22") (pin "1") (pinfunction "1_1") (pintype "passive"))
      (node (ref "IC3") (pin "3") (pinfunction "+IN_3") (pintype "input"))
      (node (ref "R17") (pin "1") (pinfunction "1_1") (pintype "passive"))
      (node (ref "REF1") (pin "1") (pinfunction "C_1") (pintype "passive"))
      (node (ref "VREF") (pin "TP") (pinfunction "P$1_TP") (pintype "bidirectional"))
    )
    (net (code "41") (name "Net-(IC6-A0)") (class "Default")
      (node (ref "IC6") (pin "1") (pinfunction "A0_1") (pintype "bidirectional"))
      (node (ref "R27") (pin "1") (pinfunction "1_1") (pintype "passive"))
      (node (ref "R28") (pin "2") (pinfunction "2_2") (pintype "passive"))
    )
    (net (code "42") (name "Net-(X2-OUT)") (class "Default")
      (node (ref "C20") (pin "1") (pinfunction "1_1") (pintype "passive"))
      (node (ref "R15") (pin "2") (pinfunction "2_2") (pintype "passive"))
      (node (ref "R16") (pin "1") (pinfunction "1_1") (pintype "passive"))
      (node (ref "X2") (pin "3") (pinfunction "OUT_3") (pintype "output"))
    )
    (net (code "43") (name "QSPI_SCLK") (class "Default")
      (node (ref "IC2") (pin "52") (pinfunction "QSPI_SCLK_52") (pintype "bidirectional"))
      (node (ref "IC4") (pin "6") (pinfunction "CLK_6") (pintype "bidirectional"))
    )
    (net (code "44") (name "QSPI_SD0") (class "Default")
      (node (ref "IC2") (pin "53") (pinfunction "QSPI_SD0_53") (pintype "bidirectional"))
      (node (ref "IC4") (pin "5") (pinfunction "DI/IO0_5") (pintype "bidirectional"))
    )
    (net (code "45") (name "QSPI_SD1") (class "Default")
      (node (ref "IC2") (pin "55") (pinfunction "QSPI_SD1_55") (pintype "bidirectional"))
      (node (ref "IC4") (pin "2") (pinfunction "DO/IO1_2") (pintype "bidirectional"))
    )
    (net (code "46") (name "QSPI_SD2") (class "Default")
      (node (ref "IC2") (pin "54") (pinfunction "QSPI_SD2_54") (pintype "bidirectional"))
      (node (ref "IC4") (pin "3") (pinfunction "~{WP}/IO2_3") (pintype "bidirectional"))
    )
    (net (code "47") (name "QSPI_SD3") (class "Default")
      (node (ref "IC2") (pin "51") (pinfunction "QSPI_SD3_51") (pintype "bidirectional"))
      (node (ref "IC4") (pin "7") (pinfunction "~{HOLD}/IO3_7") (pintype "bidirectional"))
    )
    (net (code "48") (name "RCT") (class "Default")
      (node (ref "C1") (pin "1") (pinfunction "1_1") (pintype "passive"))
      (node (ref "ETH1") (pin "5") (pinfunction "RCT_5") (pintype "passive"))
      (node (ref "R5") (pin "1") (pinfunction "1_1") (pintype "passive"))
      (node (ref "R6") (pin "1") (pinfunction "1_1") (pintype "passive"))
    )
    (net (code "49") (name "RDC_RD_N") (class "Default")
      (node (ref "C3") (pin "1") (pinfunction "1_1") (pintype "passive"))
      (node (ref "R4") (pin "2") (pinfunction "2_2") (pintype "passive"))
      (node (ref "R5") (pin "2") (pinfunction "2_2") (pintype "passive"))
    )
    (net (code "50") (name "RDC_RD_P") (class "Default")
      (node (ref "C4") (pin "1") (pinfunction "1_1") (pintype "passive"))
      (node (ref "R3") (pin "2") (pinfunction "2_2") (pintype "passive"))
      (node (ref "R6") (pin "2") (pinfunction "2_2") (pintype "passive"))
    )
    (net (code "51") (name "RD_N") (class "Default")
      (node (ref "C3") (pin "2") (pinfunction "2_2") (pintype "passive"))
      (node (ref "ETH1") (pin "6") (pinfunction "RD-_6") (pintype "passive"))
    )
    (net (code "52") (name "RD_P") (class "Default")
      (node (ref "C4") (pin "2") (pinfunction "2_2") (pintype "passive"))
      (node (ref "ETH1") (pin "4") (pinfunction "RD+_4") (pintype "passive"))
    )
    (net (code "53") (name "RP_XI") (class "Default")
      (node (ref "C19") (pin "1") (pinfunction "1_1") (pintype "passive"))
      (node (ref "IC2") (pin "20") (pinfunction "XIN_20") (pintype "bidirectional"))
      (node (ref "R15") (pin "1") (pinfunction "1_1") (pintype "passive"))
      (node (ref "X2") (pin "1") (pinfunction "CON_1") (pintype "input"))
    )
    (net (code "54") (name "RP_XO") (class "Default")
      (node (ref "IC2") (pin "21") (pinfunction "XOUT_21") (pintype "bidirectional"))
      (node (ref "R16") (pin "2") (pinfunction "2_2") (pintype "passive"))
    )
    (net (code "55") (name "RX_RD_N") (class "Default")
      (node (ref "IC1") (pin "5") (pinfunction "RXN_5") (pintype "input"))
      (node (ref "R4") (pin "1") (pinfunction "1_1") (pintype "passive"))
    )
    (net (code "56") (name "RX_RD_P") (class "Default")
      (node (ref "IC1") (pin "6") (pinfunction "RXP_6") (pintype "input"))
      (node (ref "R3") (pin "1") (pinfunction "1_1") (pintype "passive"))
    )
    (net (code "57") (name "SPI0_MISO") (class "Default")
      (node (ref "IC1") (pin "34") (pinfunction "MISO_34") (pintype "output"))
      (node (ref "IC2") (pin "27") (pinfunction "GPIO16_27") (pintype "bidirectional"))
    )
    (net (code "58") (name "SPI0_MOSI") (class "Default")
      (node (ref "IC1") (pin "35") (pinfunction "MOSI_35") (pintype "input"))
      (node (ref "IC2") (pin "30") (pinfunction "GPIO19_30") (pintype "bidirectional"))
    )
    (net (code "59") (name "SPI0_SCK") (class "Default")
      (node (ref "IC1") (pin "33") (pinfunction "SCLK_33") (pintype "input"))
      (node (ref "IC2") (pin "29") (pinfunction "GPIO18_29") (pintype "bidirectional"))
    )
    (net (code "60") (name "SWCLK") (class "Default")
      (node (ref "DBG2") (pin "1") (pinfunction "P$1_1") (pintype "bidirectional"))
      (node (ref "IC2") (pin "24") (pinfunction "SWCLK_24") (pintype "bidirectional"))
    )
    (net (code "61") (name "SWDIO") (class "Default")
      (node (ref "DBG2") (pin "3") (pinfunction "P$3_3") (pintype "bidirectional"))
      (node (ref "IC2") (pin "25") (pinfunction "SWDIO_25") (pintype "bidirectional"))
    )
    (net (code "62") (name "TCT") (class "Default")
      (node (ref "C2") (pin "1") (pinfunction "1_1") (pintype "passive"))
      (node (ref "ETH1") (pin "2") (pinfunction "TCT_2") (pintype "passive"))
      (node (ref "R40") (pin "1") (pinfunction "1_1") (pintype "passive"))
    )
    (net (code "63") (name "TD_N") (class "Default")
      (node (ref "ETH1") (pin "3") (pinfunction "TD-_3") (pintype "passive"))
      (node (ref "R1") (pin "2") (pinfunction "2_2") (pintype "passive"))
      (node (ref "R8") (pin "1") (pinfunction "1_1") (pintype "passive"))
    )
    (net (code "64") (name "TD_P") (class "Default")
      (node (ref "ETH1") (pin "1") (pinfunction "TD+_1") (pintype "passive"))
      (node (ref "R2") (pin "2") (pinfunction "2_2") (pintype "passive"))
      (node (ref "R7") (pin "1") (pinfunction "1_1") (pintype "passive"))
    )
    (net (code "65") (name "TX_TD_N") (class "Default")
      (node (ref "IC1") (pin "1") (pinfunction "TXN_1") (pintype "output"))
      (node (ref "R1") (pin "1") (pinfunction "1_1") (pintype "passive"))
    )
    (net (code "66") (name "TX_TD_P") (class "Default")
      (node (ref "IC1") (pin "2") (pinfunction "TXP_2") (pintype "output"))
      (node (ref "R2") (pin "1") (pinfunction "1_1") (pintype "passive"))
    )
    (net (code "67") (name "UART0_RX") (class "Default")
      (node (ref "DBG1") (pin "1") (pinfunction "P$1_1") (pintype "bidirectional"))
      (node (ref "IC2") (pin "2") (pinfunction "GPIO0_2") (pintype "bidirectional"))
      (node (ref "RELAYBOARD") (pin "10") (pinfunction "10_10") (pintype "passive"))
    )
    (net (code "68") (name "UART0_TX") (class "Default")
      (node (ref "DBG1") (pin "3") (pinfunction "P$3_3") (pintype "bidirectional"))
      (node (ref "IC2") (pin "3") (pinfunction "GPIO1_3") (pintype "bidirectional"))
      (node (ref "RELAYBOARD") (pin "11") (pinfunction "11_11") (pintype "passive"))
    )
    (net (code "69") (name "USB_BOOT") (class "Default")
      (node (ref "BOOT") (pin "1") (pinfunction "1_1") (pintype "passive"))
      (node (ref "BOOT") (pin "2") (pinfunction "2_2") (pintype "passive"))
      (node (ref "R19") (pin "1") (pinfunction "1_1") (pintype "passive"))
    )
    (net (code "70") (name "USB_SHIELD") (class "Default")
      (node (ref "C54") (pin "1") (pinfunction "1_1") (pintype "passive"))
      (node (ref "R39") (pin "1") (pinfunction "1_1") (pintype "passive"))
      (node (ref "USBC") (pin "S1") (pinfunction "SHIELD_S1") (pintype "passive"))
      (node (ref "USBC") (pin "S2") (pinfunction "SHIELD_S2") (pintype "passive"))
      (node (ref "USBC") (pin "S3") (pinfunction "SHIELD_S3") (pintype "passive"))
      (node (ref "USBC") (pin "S4") (pinfunction "SHIELD_S4") (pintype "passive"))
    )
    (net (code "71") (name "VBUS") (class "Default")
      (node (ref "C26") (pin "1") (pinfunction "1_1") (pintype "passive"))
      (node (ref "C27") (pin "1") (pinfunction "1_1") (pintype "passive"))
      (node (ref "C36") (pin "1") (pinfunction "1_1") (pintype "passive"))
      (node (ref "C40") (pin "1") (pinfunction "1_1") (pintype "passive"))
      (node (ref "ESD1") (pin "4") (pinfunction "C3_4") (pintype "bidirectional"))
      (node (ref "IC5") (pin "1") (pinfunction "VIN_1") (pintype "bidirectional"))
      (node (ref "IC5") (pin "3") (pinfunction "EN_3") (pintype "bidirectional"))
      (node (ref "R20") (pin "1") (pinfunction "1_1") (pintype "passive"))
      (node (ref "R25") (pin "1") (pinfunction "1_1") (pintype "passive"))
      (node (ref "USBC") (pin "A4") (pinfunction "VBUS_A4") (pintype "passive"))
      (node (ref "USBC") (pin "A9") (pinfunction "VBUS1_A9") (pintype "passive"))
      (node (ref "USBC") (pin "B4") (pinfunction "VBUS3_B4") (pintype "passive"))
      (node (ref "USBC") (pin "B9") (pinfunction "VBUS2_B9") (pintype "passive"))
      (node (ref "VBUS") (pin "TP") (pinfunction "P$1_TP") (pintype "bidirectional"))
    )
    (net (code "72") (name "V_USB") (class "Default")
      (node (ref "IC2") (pin "38") (pinfunction "GPIO26/ADC0_38") (pintype "bidirectional"))
      (node (ref "R25") (pin "2") (pinfunction "2_2") (pintype "passive"))
      (node (ref "R26") (pin "1") (pinfunction "1_1") (pintype "passive"))
    )
    (net (code "73") (name "unconnected-(IC1-DNC-Pad7)") (class "Default")
      (node (ref "IC1") (pin "7") (pinfunction "DNC_7") (pintype "bidirectional"))
    )
    (net (code "74") (name "unconnected-(IC1-DUPLED-Pad26)") (class "Default")
      (node (ref "IC1") (pin "26") (pinfunction "DUPLED_26") (pintype "output"))
    )
    (net (code "75") (name "unconnected-(IC1-RSVD1-Pad23)") (class "Default")
      (node (ref "IC1") (pin "23") (pinfunction "RSVD1_23") (pintype "input"))
    )
    (net (code "76") (name "unconnected-(IC1-RSVD2-Pad38)") (class "Default")
      (node (ref "IC1") (pin "38") (pinfunction "RSVD2_38") (pintype "input"))
    )
    (net (code "77") (name "unconnected-(IC1-RSVD3-Pad39)") (class "Default")
      (node (ref "IC1") (pin "39") (pinfunction "RSVD3_39") (pintype "input"))
    )
    (net (code "78") (name "unconnected-(IC1-RSVD4-Pad40)") (class "Default")
      (node (ref "IC1") (pin "40") (pinfunction "RSVD4_40") (pintype "input"))
    )
    (net (code "79") (name "unconnected-(IC1-RSVD5-Pad41)") (class "Default")
      (node (ref "IC1") (pin "41") (pinfunction "RSVD5_41") (pintype "input"))
    )
    (net (code "80") (name "unconnected-(IC1-RSVD6-Pad42)") (class "Default")
      (node (ref "IC1") (pin "42") (pinfunction "RSVD6_42") (pintype "input"))
    )
    (net (code "81") (name "unconnected-(IC1-SPDLED-Pad24)") (class "Default")
      (node (ref "IC1") (pin "24") (pinfunction "SPDLED_24") (pintype "output"))
    )
    (net (code "82") (name "unconnected-(IC1-VBG-Pad18)") (class "Default")
      (node (ref "IC1") (pin "18") (pinfunction "VBG_18") (pintype "output"))
    )
    (net (code "83") (name "unconnected-(IC2-GPIO25-Pad37)") (class "Default")
      (node (ref "IC2") (pin "37") (pinfunction "GPIO25_37") (pintype "bidirectional"))
    )
    (net (code "84") (name "unconnected-(IC2-GPIO27{slash}ADC1-Pad39)") (class "Default")
      (node (ref "IC2") (pin "39") (pinfunction "GPIO27/ADC1_39") (pintype "bidirectional"))
    )
    (net (code "85") (name "unconnected-(IC2-GPIO28{slash}ADC2-Pad40)") (class "Default")
      (node (ref "IC2") (pin "40") (pinfunction "GPIO28/ADC2_40") (pintype "bidirectional"))
    )
    (net (code "86") (name "unconnected-(IC5-NC-Pad4)") (class "Default")
      (node (ref "IC5") (pin "4") (pinfunction "NC_4") (pintype "bidirectional"))
    )
    (net (code "87") (name "unconnected-(RELAYBOARD-Pad17)") (class "Default")
      (node (ref "RELAYBOARD") (pin "17") (pinfunction "17_17") (pintype "passive"))
    )
    (net (code "88") (name "unconnected-(RELAYBOARD-Pad18)") (class "Default")
      (node (ref "RELAYBOARD") (pin "18") (pinfunction "18_18") (pintype "passive"))
    )
    (net (code "89") (name "unconnected-(RELAYBOARD-Pad19)") (class "Default")
      (node (ref "RELAYBOARD") (pin "19") (pinfunction "19_19") (pintype "passive"))
    )
    (net (code "90") (name "unconnected-(RELAYBOARD-Pad20)") (class "Default")
      (node (ref "RELAYBOARD") (pin "20") (pinfunction "20_20") (pintype "passive"))
    )
    (net (code "91") (name "unconnected-(USBC-SBU1-PadA8)") (class "Default")
      (node (ref "USBC") (pin "A8") (pinfunction "SBU1_A8") (pintype "passive"))
    )
    (net (code "92") (name "unconnected-(USBC-SBU2-PadB8)") (class "Default")
      (node (ref "USBC") (pin "B8") (pinfunction "SBU2_B8") (pintype "passive"))
    )
    (net (code "93") (name "~{ACT}") (class "Default")
      (node (ref "IC1") (pin "27") (pinfunction "ACTLED_27") (pintype "output"))
      (node (ref "R10") (pin "1") (pinfunction "1_1") (pintype "passive"))
    )
    (net (code "94") (name "~{INT}") (class "Default")
      (node (ref "IC1") (pin "36") (pinfunction "~{INTN}_36") (pintype "input"))
      (node (ref "IC2") (pin "32") (pinfunction "GPIO21_32") (pintype "bidirectional"))
    )
    (net (code "95") (name "~{LINK}") (class "Default")
      (node (ref "IC1") (pin "25") (pinfunction "LINKLED_25") (pintype "output"))
      (node (ref "R9") (pin "1") (pinfunction "1_1") (pintype "passive"))
    )
    (net (code "96") (name "~{QSPI_SS}") (class "Default")
      (node (ref "IC2") (pin "56") (pinfunction "QSPI_SS_N_56") (pintype "bidirectional"))
      (node (ref "IC4") (pin "1") (pinfunction "~{CS}_1") (pintype "bidirectional"))
      (node (ref "R18") (pin "1") (pinfunction "1_1") (pintype "passive"))
      (node (ref "R19") (pin "2") (pinfunction "2_2") (pintype "passive"))
    )
    (net (code "97") (name "~{RST}") (class "Default")
      (node (ref "IC1") (pin "37") (pinfunction "~{RSTN}_37") (pintype "input"))
      (node (ref "IC2") (pin "31") (pinfunction "GPIO20_31") (pintype "bidirectional"))
      (node (ref "R14") (pin "1") (pinfunction "1_1") (pintype "passive"))
    )
    (net (code "98") (name "~{SPI0_CS}") (class "Default")
      (node (ref "IC1") (pin "32") (pinfunction "~{SCSN}_32") (pintype "input"))
      (node (ref "IC2") (pin "28") (pinfunction "GPIO17_28") (pintype "bidirectional"))
    )
  )
)
